# hdmi.net
KiCad netlist of a schematic drawn in Altium Designer
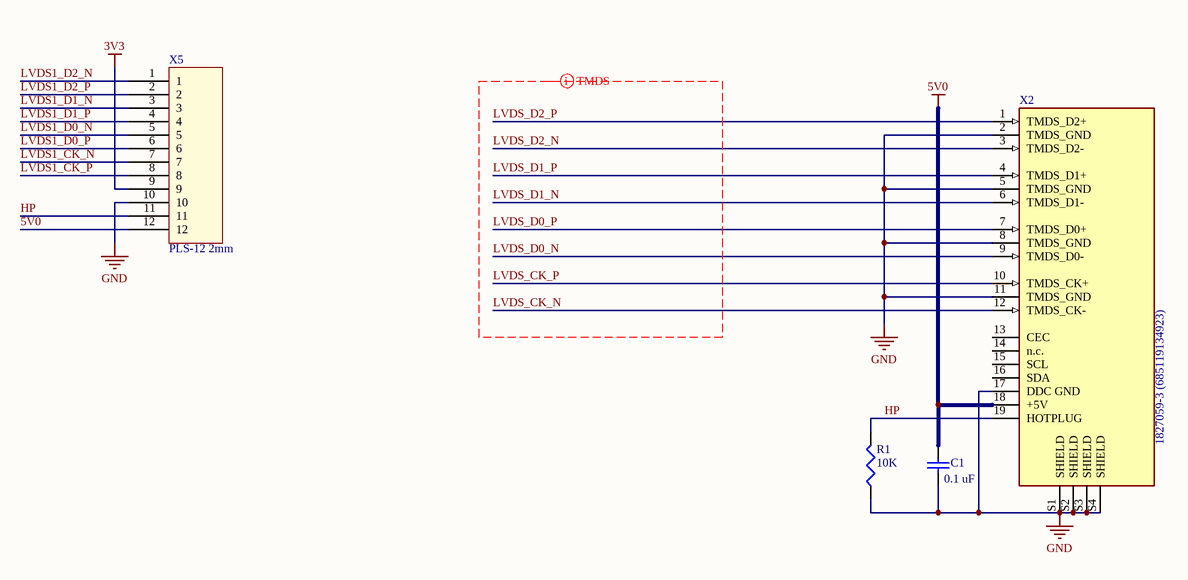
[diagram p0: hdmi.SchDoc]

(export (version "E")
  (design (tool "Eeschema 10.0.6"))
  (components
    (comp (ref "C1")
      (value "0.1 uF")
      (footprint "0805 chip cap")
      (description "Capacitor")
      (libsource (lib "Schlib") (part "Cap"))
    )
    (comp (ref "R1")
      (value "10K")
      (footprint "0805 CHIP RES")
      (description "Resistor")
      (libsource (lib "Schlib") (part "CHIP RES"))
    )
    (comp (ref "X2")
      (value "1827059-3 (685119134923)")
      (footprint "1827059-3 (685119134923)")
      (fields (field (name "MP") "SS-53000-001") (field (name "MF") "Stewart Connector"))
      (libsource (lib "Schlib") (part "1827059-3 (685119134923)"))
    )
    (comp (ref "X5")
      (value "PLS-12 2mm")
      (footprint "PLS-12 2MM")
      (libsource (lib "Schlib") (part "PLS-12 2mm"))
    )
  )
  (nets
    (net (code "1") (name "/HP") (class "Default")
      (node (ref "R1") (pin "2") (pinfunction "2_2") (pintype "passive"))
      (node (ref "X2") (pin "19") (pinfunction "HOTPLUG_19") (pintype "passive"))
      (node (ref "X5") (pin "11") (pinfunction "11_11") (pintype "passive"))
    )
    (net (code "2") (name "/LVDS1_CK_N") (class "Default")
      (node (ref "X5") (pin "7") (pinfunction "7_7") (pintype "passive"))
    )
    (net (code "3") (name "/LVDS1_CK_P") (class "Default")
      (node (ref "X5") (pin "8") (pinfunction "8_8") (pintype "passive"))
    )
    (net (code "4") (name "/LVDS1_D0_N") (class "Default")
      (node (ref "X5") (pin "5") (pinfunction "5_5") (pintype "passive"))
    )
    (net (code "5") (name "/LVDS1_D0_P") (class "Default")
      (node (ref "X5") (pin "6") (pinfunction "6_6") (pintype "passive"))
    )
    (net (code "6") (name "/LVDS1_D1_N") (class "Default")
      (node (ref "X5") (pin "3") (pinfunction "3_3") (pintype "passive"))
    )
    (net (code "7") (name "/LVDS1_D1_P") (class "Default")
      (node (ref "X5") (pin "4") (pinfunction "4_4") (pintype "passive"))
    )
    (net (code "8") (name "/LVDS1_D2_N") (class "Default")
      (node (ref "X5") (pin "1") (pinfunction "1_1") (pintype "passive"))
    )
    (net (code "9") (name "/LVDS1_D2_P") (class "Default")
      (node (ref "X5") (pin "2") (pinfunction "2_2") (pintype "passive"))
    )
    (net (code "10") (name "/LVDS_CK_N") (class "Default")
      (node (ref "X2") (pin "12") (pinfunction "TMDS_CK-_12") (pintype "input"))
    )
    (net (code "11") (name "/LVDS_CK_P") (class "Default")
      (node (ref "X2") (pin "10") (pinfunction "TMDS_CK+_10") (pintype "input"))
    )
    (net (code "12") (name "/LVDS_D0_N") (class "Default")
      (node (ref "X2") (pin "9") (pinfunction "TMDS_D0-_9") (pintype "input"))
    )
    (net (code "13") (name "/LVDS_D0_P") (class "Default")
      (node (ref "X2") (pin "7") (pinfunction "TMDS_D0+_7") (pintype "input"))
    )
    (net (code "14") (name "/LVDS_D1_N") (class "Default")
      (node (ref "X2") (pin "6") (pinfunction "TMDS_D1-_6") (pintype "input"))
    )
    (net (code "15") (name "/LVDS_D1_P") (class "Default")
      (node (ref "X2") (pin "4") (pinfunction "TMDS_D1+_4") (pintype "input"))
    )
    (net (code "16") (name "/LVDS_D2_N") (class "Default")
      (node (ref "X2") (pin "3") (pinfunction "TMDS_D2-_3") (pintype "input"))
    )
    (net (code "17") (name "/LVDS_D2_P") (class "Default")
      (node (ref "X2") (pin "1") (pinfunction "TMDS_D2+_1") (pintype "input"))
    )
    (net (code "18") (name "3V3") (class "Default")
      (node (ref "X5") (pin "9") (pinfunction "9_9") (pintype "passive"))
    )
    (net (code "19") (name "5V0") (class "Default")
      (node (ref "C1") (pin "2") (pinfunction "2_2") (pintype "passive"))
      (node (ref "X2") (pin "18") (pinfunction "+5V_18") (pintype "passive"))
      (node (ref "X5") (pin "12") (pinfunction "12_12") (pintype "passive"))
    )
    (net (code "20") (name "GND") (class "Default")
      (node (ref "C1") (pin "1") (pinfunction "1_1") (pintype "passive"))
      (node (ref "R1") (pin "1") (pinfunction "1_1") (pintype "passive"))
      (node (ref "X2") (pin "11") (pinfunction "TMDS_GND_11") (pintype "power_in"))
      (node (ref "X2") (pin "17") (pinfunction "DDC_GND_17") (pintype "passive"))
      (node (ref "X2") (pin "2") (pinfunction "TMDS_GND_2") (pintype "power_in"))
      (node (ref "X2") (pin "5") (pinfunction "TMDS_GND_5") (pintype "power_in"))
      (node (ref "X2") (pin "8") (pinfunction "TMDS_GND_8") (pintype "power_in"))
      (node (ref "X2") (pin "S1") (pinfunction "SHIELD_S1") (pintype "passive"))
      (node (ref "X2") (pin "S2") (pinfunction "SHIELD_S2") (pintype "passive"))
      (node (ref "X2") (pin "S3") (pinfunction "SHIELD_S3") (pintype "passive"))
      (node (ref "X2") (pin "S4") (pinfunction "SHIELD_S4") (pintype "passive"))
      (node (ref "X5") (pin "10") (pinfunction "10_10") (pintype "passive"))
    )
    (net (code "21") (name "unconnected-(X2-CEC-Pad13)") (class "Default")
      (node (ref "X2") (pin "13") (pinfunction "CEC_13") (pintype "passive"))
    )
    (net (code "22") (name "unconnected-(X2-SCL-Pad15)") (class "Default")
      (node (ref "X2") (pin "15") (pinfunction "SCL_15") (pintype "passive"))
    )
    (net (code "23") (name "unconnected-(X2-SDA-Pad16)") (class "Default")
      (node (ref "X2") (pin "16") (pinfunction "SDA_16") (pintype "passive"))
    )
    (net (code "24") (name "unconnected-(X2-n.c.-Pad14)") (class "Default")
      (node (ref "X2") (pin "14") (pinfunction "n.c._14") (pintype "passive"))
    )
  )
)
